# Astron_AltOsc.net
KiCad netlist of a schematic drawn in EAGLE
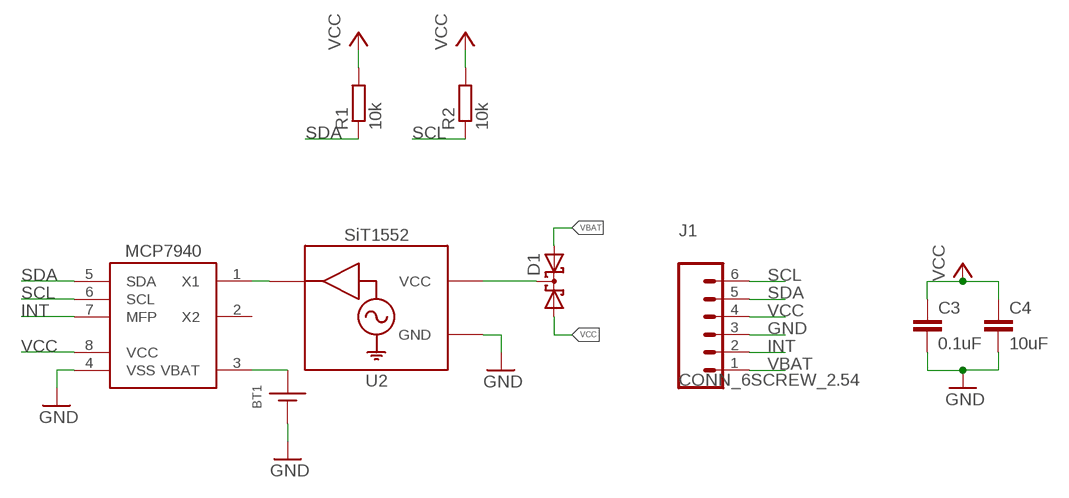
[diagram p0: schematic, sheet 1]

(export (version "E")
  (design (tool "Eeschema 10.0.6"))
  (components
    (comp (ref "BT1")
      (value "BATTERY_COIN12MM")
      (footprint "eagle-import:LINX_BAT-HLD-012-SMT")
      (fields (field (name "MF") "Linx") (field (name "MPN") "BAT-HLD-012-SMT"))
      (libsource (lib "eagle-import") (part "BATTERY_COIN12MM"))
    )
    (comp (ref "C3")
      (value "0.1uF")
      (footprint "eagle-import:C0603")
      (fields (field (name "MF") "Murata") (field (name "MPN") "GCM188R71E104KA57D"))
      (libsource (lib "eagle-import") (part "C-EUC06030.1UF"))
    )
    (comp (ref "C4")
      (value "10uF")
      (footprint "eagle-import:C0805")
      (fields (field (name "MF") "Murata") (field (name "MPN") "GRM21BR61C106KE15K"))
      (libsource (lib "eagle-import") (part "C-EUC080510UF"))
    )
    (comp (ref "D1")
      (value "DIODE_CCBAT54CSOT23")
      (footprint "eagle-import:SOT23-3")
      (fields (field (name "MF") "ON Semiconductor") (field (name "MPN") "BAT54CLT1G"))
      (libsource (lib "eagle-import") (part "DIODE_CCSOT23BAT54C"))
    )
    (comp (ref "J1")
      (value "CONN_6SCREW_2.54")
      (footprint "eagle-import:1X06_SCREW")
      (fields (field (name "MF") "OnShore") (field (name "MPN") "OSTVN06A150"))
      (libsource (lib "eagle-import") (part "CONN_6SCREW_2.54"))
    )
    (comp (ref "R1")
      (value "10k")
      (footprint "eagle-import:R0603")
      (fields (field (name "MF") "Yageo"))
      (libsource (lib "eagle-import") (part "R-EU_R0603"))
    )
    (comp (ref "R2")
      (value "10k")
      (footprint "eagle-import:R0603")
      (fields (field (name "MF") "Yageo"))
      (libsource (lib "eagle-import") (part "R-EU_R0603"))
    )
    (comp (ref "U1")
      (value "MCP7940SOIC")
      (footprint "eagle-import:SO08")
      (fields (field (name "MF") "Microchip") (field (name "MPN") "MCP7940N-I/SN"))
      (libsource (lib "eagle-import") (part "MCP7940SOIC"))
    )
    (comp (ref "U2")
      (value "SIT1552")
      (footprint "eagle-import:LD-4")
      (fields
        (field (name "DISP") "SiT1552")
        (field (name "MF") "SiTime")
        (field (name "MPN") "SIT1552AI-JF-DCC-32.768D")
      )
      (libsource (lib "eagle-import") (part "SIT1552"))
    )
  )
  (nets
    (net (code "1") (name "/INT") (class "Default")
      (node (ref "J1") (pin "2") (pinfunction "2_2") (pintype "passive"))
      (node (ref "U1") (pin "7") (pinfunction "MFP_7") (pintype "bidirectional"))
    )
    (net (code "2") (name "/SCL") (class "Default")
      (node (ref "J1") (pin "6") (pinfunction "6_6") (pintype "passive"))
      (node (ref "R2") (pin "1") (pinfunction "1_1") (pintype "passive"))
      (node (ref "U1") (pin "6") (pinfunction "SCL_6") (pintype "bidirectional"))
    )
    (net (code "3") (name "/SDA") (class "Default")
      (node (ref "J1") (pin "5") (pinfunction "5_5") (pintype "passive"))
      (node (ref "R1") (pin "1") (pinfunction "1_1") (pintype "passive"))
      (node (ref "U1") (pin "5") (pinfunction "SDA_5") (pintype "bidirectional"))
    )
    (net (code "4") (name "GND") (class "Default")
      (node (ref "BT1") (pin "GND") (pinfunction "-_GND") (pintype "power_in"))
      (node (ref "C3") (pin "2") (pinfunction "2_2") (pintype "passive"))
      (node (ref "C4") (pin "2") (pinfunction "2_2") (pintype "passive"))
      (node (ref "J1") (pin "3") (pinfunction "3_3") (pintype "passive"))
      (node (ref "U1") (pin "4") (pinfunction "VSS_4") (pintype "bidirectional"))
      (node (ref "U2") (pin "1") (pinfunction "GND_1") (pintype "power_in"))
      (node (ref "U2") (pin "4") (pinfunction "GND_4") (pintype "power_in"))
    )
    (net (code "5") (name "Net-(D1-C)") (class "Default")
      (node (ref "D1") (pin "3") (pinfunction "C_3") (pintype "passive"))
      (node (ref "U2") (pin "3") (pinfunction "VCC_3") (pintype "power_in"))
    )
    (net (code "6") (name "Net-(U1-X1)") (class "Default")
      (node (ref "U1") (pin "1") (pinfunction "X1_1") (pintype "bidirectional"))
      (node (ref "U2") (pin "2") (pinfunction "CLK_2") (pintype "output"))
    )
    (net (code "7") (name "VBAT") (class "Default")
      (node (ref "BT1") (pin "POWER0") (pinfunction "+_POWER0") (pintype "power_in"))
      (node (ref "BT1") (pin "POWER1") (pinfunction "+_POWER1") (pintype "power_in"))
      (node (ref "D1") (pin "2") (pinfunction "A2_2") (pintype "passive"))
      (node (ref "J1") (pin "1") (pinfunction "1_1") (pintype "passive"))
      (node (ref "U1") (pin "3") (pinfunction "VBAT_3") (pintype "bidirectional"))
    )
    (net (code "8") (name "VCC") (class "Default")
      (node (ref "C3") (pin "1") (pinfunction "1_1") (pintype "passive"))
      (node (ref "C4") (pin "1") (pinfunction "1_1") (pintype "passive"))
      (node (ref "D1") (pin "1") (pinfunction "A1_1") (pintype "passive"))
      (node (ref "J1") (pin "4") (pinfunction "4_4") (pintype "passive"))
      (node (ref "R1") (pin "2") (pinfunction "2_2") (pintype "passive"))
      (node (ref "R2") (pin "2") (pinfunction "2_2") (pintype "passive"))
      (node (ref "U1") (pin "8") (pinfunction "VCC_8") (pintype "bidirectional"))
    )
    (net (code "9") (name "unconnected-(U1-X2-Pad2)") (class "Default")
      (node (ref "U1") (pin "2") (pinfunction "X2_2") (pintype "bidirectional"))
    )
  )
)
